# Stepstick.net
KiCad netlist of a schematic drawn in Altium Designer
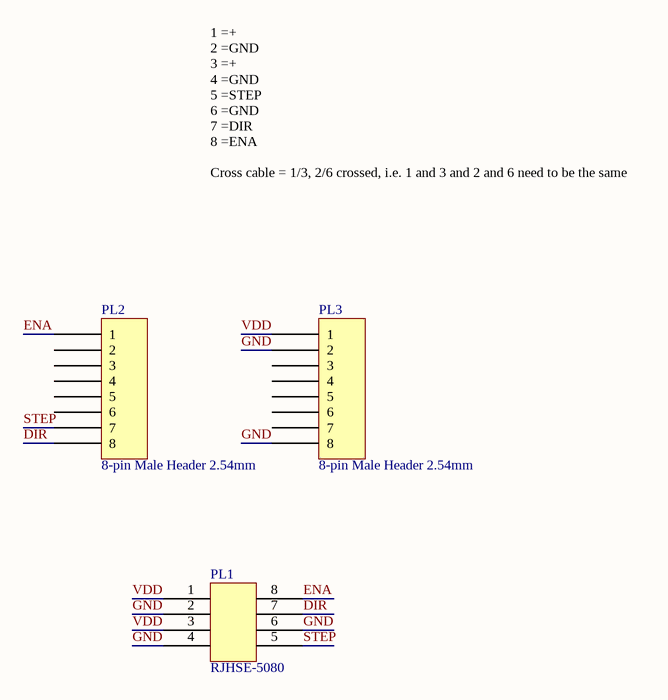
[diagram p0: Stepstick.SchDoc]

(export (version "E")
  (design (tool "Eeschema 10.0.6"))
  (components
    (comp (ref "PL1")
      (value "RJHSE-5080")
      (footprint "AMPHENOL RJHSE-5080")
      (description "CONN MOD JACK 8P8C R/A UNSHLD")
      (libsource (lib "ON Development Vault") (part "2x4"))
    )
    (comp (ref "PL2")
      (value "8-pin Male Header 2.54mm")
      (footprint "8-pin 2.54mm header")
      (description "8 Positions Header Connector 0.100\" (2.54mm) Through Hole Gold")
      (libsource (lib "ON Development Vault") (part "8Pin Header"))
    )
    (comp (ref "PL3")
      (value "8-pin Male Header 2.54mm")
      (footprint "8-pin 2.54mm header")
      (description "8 Positions Header Connector 0.100\" (2.54mm) Through Hole Gold")
      (libsource (lib "ON Development Vault") (part "8Pin Header"))
    )
  )
  (nets
    (net (code "1") (name "/DIR") (class "Default")
      (node (ref "PL1") (pin "7") (pinfunction "7_7") (pintype "passive"))
      (node (ref "PL2") (pin "8") (pinfunction "8_8") (pintype "passive"))
    )
    (net (code "2") (name "/ENA") (class "Default")
      (node (ref "PL1") (pin "8") (pinfunction "8_8") (pintype "passive"))
      (node (ref "PL2") (pin "1") (pinfunction "1_1") (pintype "passive"))
    )
    (net (code "3") (name "/GND") (class "Default")
      (node (ref "PL1") (pin "2") (pinfunction "2_2") (pintype "passive"))
      (node (ref "PL1") (pin "4") (pinfunction "4_4") (pintype "passive"))
      (node (ref "PL1") (pin "6") (pinfunction "6_6") (pintype "passive"))
      (node (ref "PL3") (pin "2") (pinfunction "2_2") (pintype "passive"))
      (node (ref "PL3") (pin "8") (pinfunction "8_8") (pintype "passive"))
    )
    (net (code "4") (name "/STEP") (class "Default")
      (node (ref "PL1") (pin "5") (pinfunction "5_5") (pintype "passive"))
      (node (ref "PL2") (pin "7") (pinfunction "7_7") (pintype "passive"))
    )
    (net (code "5") (name "/VDD") (class "Default")
      (node (ref "PL1") (pin "1") (pinfunction "1_1") (pintype "passive"))
      (node (ref "PL1") (pin "3") (pinfunction "3_3") (pintype "passive"))
      (node (ref "PL3") (pin "1") (pinfunction "1_1") (pintype "passive"))
    )
    (net (code "6") (name "unconnected-(PL2-Pad2)") (class "Default")
      (node (ref "PL2") (pin "2") (pinfunction "2_2") (pintype "passive"))
    )
    (net (code "7") (name "unconnected-(PL2-Pad3)") (class "Default")
      (node (ref "PL2") (pin "3") (pinfunction "3_3") (pintype "passive"))
    )
    (net (code "8") (name "unconnected-(PL2-Pad4)") (class "Default")
      (node (ref "PL2") (pin "4") (pinfunction "4_4") (pintype "passive"))
    )
    (net (code "9") (name "unconnected-(PL2-Pad5)") (class "Default")
      (node (ref "PL2") (pin "5") (pinfunction "5_5") (pintype "passive"))
    )
    (net (code "10") (name "unconnected-(PL2-Pad6)") (class "Default")
      (node (ref "PL2") (pin "6") (pinfunction "6_6") (pintype "passive"))
    )
    (net (code "11") (name "unconnected-(PL3-Pad3)") (class "Default")
      (node (ref "PL3") (pin "3") (pinfunction "3_3") (pintype "passive"))
    )
    (net (code "12") (name "unconnected-(PL3-Pad4)") (class "Default")
      (node (ref "PL3") (pin "4") (pinfunction "4_4") (pintype "passive"))
    )
    (net (code "13") (name "unconnected-(PL3-Pad5)") (class "Default")
      (node (ref "PL3") (pin "5") (pinfunction "5_5") (pintype "passive"))
    )
    (net (code "14") (name "unconnected-(PL3-Pad6)") (class "Default")
      (node (ref "PL3") (pin "6") (pinfunction "6_6") (pintype "passive"))
    )
    (net (code "15") (name "unconnected-(PL3-Pad7)") (class "Default")
      (node (ref "PL3") (pin "7") (pinfunction "7_7") (pintype "passive"))
    )
  )
)
